# Sat_Cape_v7.net
KiCad netlist of a schematic drawn in EAGLE
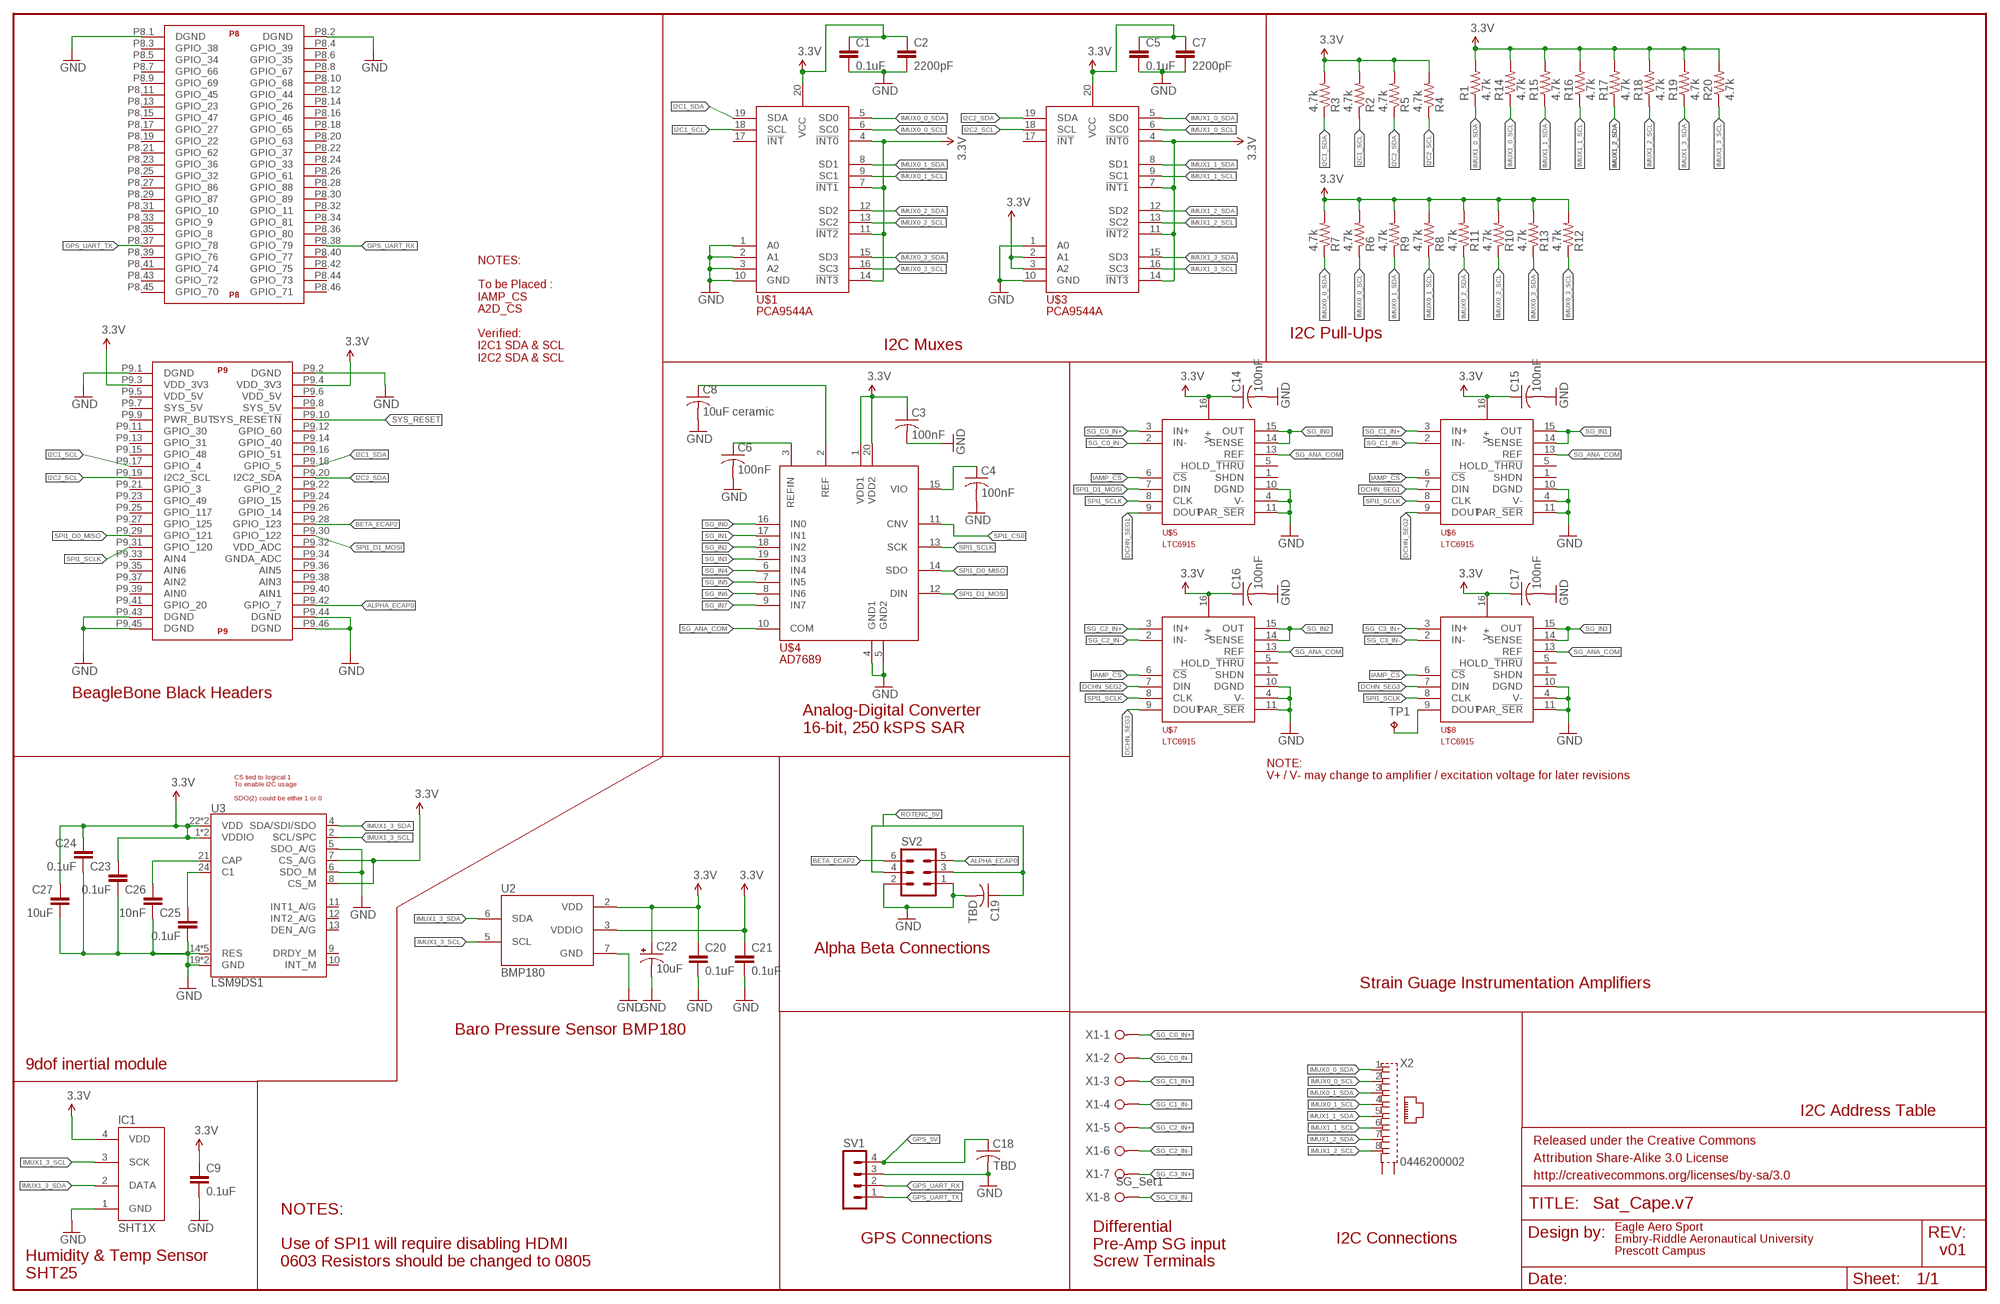
[diagram p0: schematic, sheet 1]

(export (version "E")
  (design (tool "Eeschema 10.0.6"))
  (components
    (comp (ref "C1")
      (value "0.1uF")
      (footprint "eagle-import:0603-CAP")
      (libsource (lib "eagle-import") (part "0.1UF-25V(+80/-20%)(0603)"))
    )
    (comp (ref "C2")
      (value "2200pF")
      (footprint "eagle-import:0603-CAP")
      (libsource (lib "eagle-import") (part "0.1UF-25V(+80/-20%)(0603)"))
    )
    (comp (ref "C3")
      (value "100nF")
      (footprint "eagle-import:C0805")
      (libsource (lib "eagle-import") (part "C-USC0805"))
    )
    (comp (ref "C4")
      (value "100nF")
      (footprint "eagle-import:C0805")
      (libsource (lib "eagle-import") (part "C-USC0805"))
    )
    (comp (ref "C5")
      (value "0.1uF")
      (footprint "eagle-import:0603-CAP")
      (libsource (lib "eagle-import") (part "0.1UF-25V(+80/-20%)(0603)"))
    )
    (comp (ref "C6")
      (value "100nF")
      (footprint "eagle-import:C0805")
      (libsource (lib "eagle-import") (part "C-USC0805"))
    )
    (comp (ref "C7")
      (value "2200pF")
      (footprint "eagle-import:0603-CAP")
      (libsource (lib "eagle-import") (part "0.1UF-25V(+80/-20%)(0603)"))
    )
    (comp (ref "C8")
      (value "10uF ceramic")
      (footprint "eagle-import:C0805")
      (libsource (lib "eagle-import") (part "C-USC0805"))
    )
    (comp (ref "C9")
      (value "0.1uF")
      (footprint "eagle-import:0603-CAP")
      (libsource (lib "eagle-import") (part "0.1UF-25V(+80/-20%)(0603)"))
    )
    (comp (ref "C14")
      (value "100nF")
      (footprint "eagle-import:C0805")
      (libsource (lib "eagle-import") (part "C-USC0805"))
    )
    (comp (ref "C15")
      (value "100nF")
      (footprint "eagle-import:C0805")
      (libsource (lib "eagle-import") (part "C-USC0805"))
    )
    (comp (ref "C16")
      (value "100nF")
      (footprint "eagle-import:C0805")
      (libsource (lib "eagle-import") (part "C-USC0805"))
    )
    (comp (ref "C17")
      (value "100nF")
      (footprint "eagle-import:C0805")
      (libsource (lib "eagle-import") (part "C-USC0805"))
    )
    (comp (ref "C18")
      (value "TBD")
      (footprint "eagle-import:C0805")
      (libsource (lib "eagle-import") (part "C-USC0805"))
    )
    (comp (ref "C19")
      (value "TBD")
      (footprint "eagle-import:C0805")
      (libsource (lib "eagle-import") (part "C-USC0805"))
    )
    (comp (ref "C20")
      (value "0.1uF")
      (footprint "eagle-import:0603-CAP")
      (libsource (lib "eagle-import") (part "CAP0603-CAP"))
    )
    (comp (ref "C21")
      (value "0.1uF")
      (footprint "eagle-import:0603-CAP")
      (libsource (lib "eagle-import") (part "CAP0603-CAP"))
    )
    (comp (ref "C22")
      (value "10uF")
      (footprint "eagle-import:EIA3216")
      (libsource (lib "eagle-import") (part "10UF-16V-10%(TANT)"))
    )
    (comp (ref "C23")
      (value "0.1uF")
      (footprint "eagle-import:0603-CAP")
      (libsource (lib "eagle-import") (part "0.1UF-25V(+80/-20%)(0603)"))
    )
    (comp (ref "C24")
      (value "0.1uF")
      (footprint "eagle-import:0603-CAP")
      (libsource (lib "eagle-import") (part "0.1UF-25V(+80/-20%)(0603)"))
    )
    (comp (ref "C25")
      (value "0.1uF")
      (footprint "eagle-import:0603-CAP")
      (libsource (lib "eagle-import") (part "0.1UF-25V(+80/-20%)(0603)"))
    )
    (comp (ref "C26")
      (value "10nF")
      (footprint "eagle-import:0603-CAP")
      (libsource (lib "eagle-import") (part "10NF/10000PF-50V-10%(0603)"))
    )
    (comp (ref "C27")
      (value "10uF")
      (footprint "eagle-import:0603-CAP")
      (libsource (lib "eagle-import") (part "10UF-6.3V-20%(0603)"))
    )
    (comp (ref "FRAME1")
      (value "FRAME-LEDGER")
      (footprint "eagle-import:CREATIVE_COMMONS")
      (libsource (lib "eagle-import") (part "FRAME-LEDGER"))
    )
    (comp (ref "IC1")
      (value "SHT1X")
      (footprint "eagle-import:SHT1X")
      (libsource (lib "eagle-import") (part "SHT1X"))
    )
    (comp (ref "R1")
      (value "4.7k")
      (footprint "eagle-import:R0805")
      (libsource (lib "eagle-import") (part "R-US_R0805"))
    )
    (comp (ref "R2")
      (value "4.7k")
      (footprint "eagle-import:0603-RES")
      (libsource (lib "eagle-import") (part "10KOHM1/10W1%(0603)0603"))
    )
    (comp (ref "R3")
      (value "4.7k")
      (footprint "eagle-import:0603-RES")
      (libsource (lib "eagle-import") (part "10KOHM1/10W1%(0603)0603"))
    )
    (comp (ref "R4")
      (value "4.7k")
      (footprint "eagle-import:0603-RES")
      (libsource (lib "eagle-import") (part "10KOHM1/10W1%(0603)0603"))
    )
    (comp (ref "R5")
      (value "4.7k")
      (footprint "eagle-import:0603-RES")
      (libsource (lib "eagle-import") (part "10KOHM1/10W1%(0603)0603"))
    )
    (comp (ref "R6")
      (value "4.7k")
      (footprint "eagle-import:0603-RES")
      (libsource (lib "eagle-import") (part "10KOHM1/10W1%(0603)0603"))
    )
    (comp (ref "R7")
      (value "4.7k")
      (footprint "eagle-import:0603-RES")
      (libsource (lib "eagle-import") (part "10KOHM1/10W1%(0603)0603"))
    )
    (comp (ref "R8")
      (value "4.7k")
      (footprint "eagle-import:0603-RES")
      (libsource (lib "eagle-import") (part "10KOHM1/10W1%(0603)0603"))
    )
    (comp (ref "R9")
      (value "4.7k")
      (footprint "eagle-import:0603-RES")
      (libsource (lib "eagle-import") (part "10KOHM1/10W1%(0603)0603"))
    )
    (comp (ref "R10")
      (value "4.7k")
      (footprint "eagle-import:0603-RES")
      (libsource (lib "eagle-import") (part "10KOHM1/10W1%(0603)0603"))
    )
    (comp (ref "R11")
      (value "4.7k")
      (footprint "eagle-import:0603-RES")
      (libsource (lib "eagle-import") (part "10KOHM1/10W1%(0603)0603"))
    )
    (comp (ref "R12")
      (value "4.7k")
      (footprint "eagle-import:0603-RES")
      (libsource (lib "eagle-import") (part "10KOHM1/10W1%(0603)0603"))
    )
    (comp (ref "R13")
      (value "4.7k")
      (footprint "eagle-import:0603-RES")
      (libsource (lib "eagle-import") (part "10KOHM1/10W1%(0603)0603"))
    )
    (comp (ref "R14")
      (value "4.7k")
      (footprint "eagle-import:R0805")
      (libsource (lib "eagle-import") (part "R-US_R0805"))
    )
    (comp (ref "R15")
      (value "4.7k")
      (footprint "eagle-import:R0805")
      (libsource (lib "eagle-import") (part "R-US_R0805"))
    )
    (comp (ref "R16")
      (value "4.7k")
      (footprint "eagle-import:R0805")
      (libsource (lib "eagle-import") (part "R-US_R0805"))
    )
    (comp (ref "R17")
      (value "4.7k")
      (footprint "eagle-import:R0805")
      (libsource (lib "eagle-import") (part "R-US_R0805"))
    )
    (comp (ref "R18")
      (value "4.7k")
      (footprint "eagle-import:R0805")
      (libsource (lib "eagle-import") (part "R-US_R0805"))
    )
    (comp (ref "R19")
      (value "4.7k")
      (footprint "eagle-import:R0805")
      (libsource (lib "eagle-import") (part "R-US_R0805"))
    )
    (comp (ref "R20")
      (value "4.7k")
      (footprint "eagle-import:R0805")
      (libsource (lib "eagle-import") (part "R-US_R0805"))
    )
    (comp (ref "SV1")
      (value "MA04-1")
      (footprint "eagle-import:MA04-1")
      (libsource (lib "eagle-import") (part "MA04-1"))
    )
    (comp (ref "SV2")
      (value "MA03-2")
      (footprint "eagle-import:MA03-2")
      (libsource (lib "eagle-import") (part "MA03-2"))
    )
    (comp (ref "TP1")
      (value "TPTP08R")
      (footprint "eagle-import:TP08R")
      (libsource (lib "eagle-import") (part "TPTP08R"))
    )
    (comp (ref "U$1")
      (value "PCA9544A")
      (footprint "eagle-import:TSSOP20")
      (libsource (lib "eagle-import") (part "PCA9544A"))
    )
    (comp (ref "U$2")
      (value "BEAGLE_BONE_BLACK_CAPE")
      (footprint "eagle-import:BEAGLE_BONE_BLACK_CAPE")
      (libsource (lib "eagle-import") (part "BEAGLE_BONE_BLACK_CAPE"))
    )
    (comp (ref "U$3")
      (value "PCA9544A")
      (footprint "eagle-import:TSSOP20")
      (libsource (lib "eagle-import") (part "PCA9544A"))
    )
    (comp (ref "U$4")
      (value "AD7689")
      (footprint "eagle-import:QFN20")
      (libsource (lib "eagle-import") (part "AD7689"))
    )
    (comp (ref "U$5")
      (value "LTC6915")
      (footprint "eagle-import:SSOP16")
      (libsource (lib "eagle-import") (part "LTC6915"))
    )
    (comp (ref "U$6")
      (value "LTC6915")
      (footprint "eagle-import:SSOP16")
      (libsource (lib "eagle-import") (part "LTC6915"))
    )
    (comp (ref "U$7")
      (value "LTC6915")
      (footprint "eagle-import:SSOP16")
      (libsource (lib "eagle-import") (part "LTC6915"))
    )
    (comp (ref "U$8")
      (value "LTC6915")
      (footprint "eagle-import:SSOP16")
      (libsource (lib "eagle-import") (part "LTC6915"))
    )
    (comp (ref "U2")
      (value "BMP180")
      (footprint "eagle-import:BMP180")
      (libsource (lib "eagle-import") (part "BMP180"))
    )
    (comp (ref "U3")
      (value "LSM9DS1")
      (footprint "eagle-import:LGA24-8X4")
      (libsource (lib "eagle-import") (part "LSM9DS1"))
    )
    (comp (ref "X1")
      (value "SG_Set1")
      (footprint "eagle-import:W237-8P")
      (libsource (lib "eagle-import") (part "W237-08P"))
    )
    (comp (ref "X2")
      (value "0446200002")
      (footprint "eagle-import:0446200002")
      (fields (field (name "MF") "MOLEX"))
      (libsource (lib "eagle-import") (part "0446200002"))
    )
  )
  (nets
    (net (code "1") (name "/IAMP_~{CS}") (class "Default")
      (node (ref "U$5") (pin "6") (pinfunction "~{CS}_6") (pintype "bidirectional"))
      (node (ref "U$6") (pin "6") (pinfunction "~{CS}_6") (pintype "bidirectional"))
      (node (ref "U$7") (pin "6") (pinfunction "~{CS}_6") (pintype "bidirectional"))
      (node (ref "U$8") (pin "6") (pinfunction "~{CS}_6") (pintype "bidirectional"))
    )
    (net (code "2") (name "3.3V") (class "Default")
      (node (ref "C1") (pin "1") (pinfunction "1_1") (pintype "passive"))
      (node (ref "C14") (pin "1") (pinfunction "1_1") (pintype "passive"))
      (node (ref "C15") (pin "1") (pinfunction "1_1") (pintype "passive"))
      (node (ref "C16") (pin "1") (pinfunction "1_1") (pintype "passive"))
      (node (ref "C17") (pin "1") (pinfunction "1_1") (pintype "passive"))
      (node (ref "C2") (pin "1") (pinfunction "1_1") (pintype "passive"))
      (node (ref "C20") (pin "1") (pinfunction "1_1") (pintype "passive"))
      (node (ref "C21") (pin "1") (pinfunction "1_1") (pintype "passive"))
      (node (ref "C22") (pin "A") (pinfunction "+_A") (pintype "passive"))
      (node (ref "C23") (pin "1") (pinfunction "1_1") (pintype "passive"))
      (node (ref "C24") (pin "1") (pinfunction "1_1") (pintype "passive"))
      (node (ref "C27") (pin "1") (pinfunction "1_1") (pintype "passive"))
      (node (ref "C3") (pin "1") (pinfunction "1_1") (pintype "passive"))
      (node (ref "C5") (pin "1") (pinfunction "1_1") (pintype "passive"))
      (node (ref "C7") (pin "1") (pinfunction "1_1") (pintype "passive"))
      (node (ref "C9") (pin "1") (pinfunction "1_1") (pintype "passive"))
      (node (ref "IC1") (pin "4") (pinfunction "VDD_4") (pintype "power_in"))
      (node (ref "R1") (pin "2") (pinfunction "2_2") (pintype "passive"))
      (node (ref "R10") (pin "2") (pinfunction "2_2") (pintype "passive"))
      (node (ref "R11") (pin "2") (pinfunction "2_2") (pintype "passive"))
      (node (ref "R12") (pin "2") (pinfunction "2_2") (pintype "passive"))
      (node (ref "R13") (pin "2") (pinfunction "2_2") (pintype "passive"))
      (node (ref "R14") (pin "2") (pinfunction "2_2") (pintype "passive"))
      (node (ref "R15") (pin "2") (pinfunction "2_2") (pintype "passive"))
      (node (ref "R16") (pin "2") (pinfunction "2_2") (pintype "passive"))
      (node (ref "R17") (pin "2") (pinfunction "2_2") (pintype "passive"))
      (node (ref "R18") (pin "2") (pinfunction "2_2") (pintype "passive"))
      (node (ref "R19") (pin "2") (pinfunction "2_2") (pintype "passive"))
      (node (ref "R2") (pin "2") (pinfunction "2_2") (pintype "passive"))
      (node (ref "R20") (pin "2") (pinfunction "2_2") (pintype "passive"))
      (node (ref "R3") (pin "2") (pinfunction "2_2") (pintype "passive"))
      (node (ref "R4") (pin "2") (pinfunction "2_2") (pintype "passive"))
      (node (ref "R5") (pin "2") (pinfunction "2_2") (pintype "passive"))
      (node (ref "R6") (pin "2") (pinfunction "2_2") (pintype "passive"))
      (node (ref "R7") (pin "2") (pinfunction "2_2") (pintype "passive"))
      (node (ref "R8") (pin "2") (pinfunction "2_2") (pintype "passive"))
      (node (ref "R9") (pin "2") (pinfunction "2_2") (pintype "passive"))
      (node (ref "U$1") (pin "11") (pinfunction "~{INT2}_11") (pintype "input"))
      (node (ref "U$1") (pin "14") (pinfunction "~{INT3}_14") (pintype "input"))
      (node (ref "U$1") (pin "20") (pinfunction "VCC_20") (pintype "power_in"))
      (node (ref "U$1") (pin "4") (pinfunction "~{INT0}_4") (pintype "input"))
      (node (ref "U$1") (pin "7") (pinfunction "~{INT1}_7") (pintype "input"))
      (node (ref "U$2") (pin "P9.3") (pinfunction "VDD_3V3_P9.3") (pintype "bidirectional"))
      (node (ref "U$2") (pin "P9.4") (pinfunction "VDD_3V3_P9.4") (pintype "bidirectional"))
      (node (ref "U$3") (pin "11") (pinfunction "~{INT2}_11") (pintype "input"))
      (node (ref "U$3") (pin "14") (pinfunction "~{INT3}_14") (pintype "input"))
      (node (ref "U$3") (pin "2") (pinfunction "A1_2") (pintype "input"))
      (node (ref "U$3") (pin "20") (pinfunction "VCC_20") (pintype "power_in"))
      (node (ref "U$3") (pin "3") (pinfunction "A2_3") (pintype "input"))
      (node (ref "U$3") (pin "4") (pinfunction "~{INT0}_4") (pintype "input"))
      (node (ref "U$3") (pin "7") (pinfunction "~{INT1}_7") (pintype "input"))
      (node (ref "U$4") (pin "1") (pinfunction "VDD1_1") (pintype "bidirectional"))
      (node (ref "U$4") (pin "20") (pinfunction "VDD2_20") (pintype "bidirectional"))
      (node (ref "U$5") (pin "16") (pinfunction "V+_16") (pintype "bidirectional"))
      (node (ref "U$6") (pin "16") (pinfunction "V+_16") (pintype "bidirectional"))
      (node (ref "U$7") (pin "16") (pinfunction "V+_16") (pintype "bidirectional"))
      (node (ref "U$8") (pin "16") (pinfunction "V+_16") (pintype "bidirectional"))
      (node (ref "U2") (pin "2") (pinfunction "VDD_2") (pintype "power_in"))
      (node (ref "U2") (pin "3") (pinfunction "VDDIO_3") (pintype "power_in"))
      (node (ref "U3") (pin "1") (pinfunction "VDDIO_1") (pintype "bidirectional"))
      (node (ref "U3") (pin "22") (pinfunction "VDD_22") (pintype "bidirectional"))
      (node (ref "U3") (pin "23") (pinfunction "VDD_23") (pintype "bidirectional"))
      (node (ref "U3") (pin "3") (pinfunction "VDDIO_3") (pintype "bidirectional"))
      (node (ref "U3") (pin "7") (pinfunction "CS_A/G_7") (pintype "bidirectional"))
      (node (ref "U3") (pin "8") (pinfunction "CS_M_8") (pintype "bidirectional"))
    )
    (net (code "3") (name "ALPHA_ECAP0") (class "Default")
      (node (ref "SV2") (pin "5") (pinfunction "5_5") (pintype "passive"))
      (node (ref "U$2") (pin "P9.42") (pinfunction "GPIO_7_P9.42") (pintype "bidirectional"))
    )
    (net (code "4") (name "BETA_ECAP2") (class "Default")
      (node (ref "SV2") (pin "6") (pinfunction "6_6") (pintype "passive"))
      (node (ref "U$2") (pin "P9.28") (pinfunction "GPIO_123_P9.28") (pintype "bidirectional"))
    )
    (net (code "5") (name "DCHN_SEG1") (class "Default")
      (node (ref "U$5") (pin "9") (pinfunction "DOUT_9") (pintype "bidirectional"))
      (node (ref "U$6") (pin "7") (pinfunction "DIN_7") (pintype "bidirectional"))
    )
    (net (code "6") (name "DCHN_SEG2") (class "Default")
      (node (ref "U$6") (pin "9") (pinfunction "DOUT_9") (pintype "bidirectional"))
      (node (ref "U$7") (pin "7") (pinfunction "DIN_7") (pintype "bidirectional"))
    )
    (net (code "7") (name "DCHN_SEG3") (class "Default")
      (node (ref "U$7") (pin "9") (pinfunction "DOUT_9") (pintype "bidirectional"))
      (node (ref "U$8") (pin "7") (pinfunction "DIN_7") (pintype "bidirectional"))
    )
    (net (code "8") (name "GND") (class "Default")
      (node (ref "C1") (pin "2") (pinfunction "2_2") (pintype "passive"))
      (node (ref "C14") (pin "2") (pinfunction "2_2") (pintype "passive"))
      (node (ref "C15") (pin "2") (pinfunction "2_2") (pintype "passive"))
      (node (ref "C16") (pin "2") (pinfunction "2_2") (pintype "passive"))
      (node (ref "C17") (pin "2") (pinfunction "2_2") (pintype "passive"))
      (node (ref "C18") (pin "2") (pinfunction "2_2") (pintype "passive"))
      (node (ref "C19") (pin "2") (pinfunction "2_2") (pintype "passive"))
      (node (ref "C2") (pin "2") (pinfunction "2_2") (pintype "passive"))
      (node (ref "C20") (pin "2") (pinfunction "2_2") (pintype "passive"))
      (node (ref "C21") (pin "2") (pinfunction "2_2") (pintype "passive"))
      (node (ref "C22") (pin "C") (pinfunction "-_C") (pintype "passive"))
      (node (ref "C23") (pin "2") (pinfunction "2_2") (pintype "passive"))
      (node (ref "C24") (pin "2") (pinfunction "2_2") (pintype "passive"))
      (node (ref "C25") (pin "2") (pinfunction "2_2") (pintype "passive"))
      (node (ref "C26") (pin "2") (pinfunction "2_2") (pintype "passive"))
      (node (ref "C27") (pin "2") (pinfunction "2_2") (pintype "passive"))
      (node (ref "C3") (pin "2") (pinfunction "2_2") (pintype "passive"))
      (node (ref "C4") (pin "2") (pinfunction "2_2") (pintype "passive"))
      (node (ref "C5") (pin "2") (pinfunction "2_2") (pintype "passive"))
      (node (ref "C6") (pin "2") (pinfunction "2_2") (pintype "passive"))
      (node (ref "C7") (pin "2") (pinfunction "2_2") (pintype "passive"))
      (node (ref "C8") (pin "2") (pinfunction "2_2") (pintype "passive"))
      (node (ref "C9") (pin "2") (pinfunction "2_2") (pintype "passive"))
      (node (ref "IC1") (pin "1") (pinfunction "GND_1") (pintype "power_in"))
      (node (ref "SV1") (pin "3") (pinfunction "3_3") (pintype "passive"))
      (node (ref "SV2") (pin "1") (pinfunction "1_1") (pintype "passive"))
      (node (ref "SV2") (pin "2") (pinfunction "2_2") (pintype "passive"))
      (node (ref "U$1") (pin "1") (pinfunction "A0_1") (pintype "input"))
      (node (ref "U$1") (pin "10") (pinfunction "GND_10") (pintype "power_in"))
      (node (ref "U$1") (pin "2") (pinfunction "A1_2") (pintype "input"))
      (node (ref "U$1") (pin "3") (pinfunction "A2_3") (pintype "input"))
      (node (ref "U$2") (pin "P8.1") (pinfunction "DGND_P8.1") (pintype "bidirectional"))
      (node (ref "U$2") (pin "P8.2") (pinfunction "DGND_P8.2") (pintype "bidirectional"))
      (node (ref "U$2") (pin "P9.1") (pinfunction "DGND_P9.1") (pintype "bidirectional"))
      (node (ref "U$2") (pin "P9.2") (pinfunction "DGND_P9.2") (pintype "bidirectional"))
      (node (ref "U$2") (pin "P9.43") (pinfunction "DGND_P9.43") (pintype "bidirectional"))
      (node (ref "U$2") (pin "P9.44") (pinfunction "DGND_P9.44") (pintype "bidirectional"))
      (node (ref "U$2") (pin "P9.45") (pinfunction "DGND_P9.45") (pintype "bidirectional"))
      (node (ref "U$2") (pin "P9.46") (pinfunction "DGND_P9.46") (pintype "bidirectional"))
      (node (ref "U$3") (pin "1") (pinfunction "A0_1") (pintype "input"))
      (node (ref "U$3") (pin "10") (pinfunction "GND_10") (pintype "power_in"))
      (node (ref "U$4") (pin "4") (pinfunction "GND1_4") (pintype "bidirectional"))
      (node (ref "U$4") (pin "5") (pinfunction "GND2_5") (pintype "bidirectional"))
      (node (ref "U$5") (pin "10") (pinfunction "DGND_10") (pintype "bidirectional"))
      (node (ref "U$5") (pin "11") (pinfunction "PAR_~{SER}_11") (pintype "bidirectional"))
      (node (ref "U$5") (pin "4") (pinfunction "V-_4") (pintype "bidirectional"))
      (node (ref "U$6") (pin "10") (pinfunction "DGND_10") (pintype "bidirectional"))
      (node (ref "U$6") (pin "11") (pinfunction "PAR_~{SER}_11") (pintype "bidirectional"))
      (node (ref "U$6") (pin "4") (pinfunction "V-_4") (pintype "bidirectional"))
      (node (ref "U$7") (pin "10") (pinfunction "DGND_10") (pintype "bidirectional"))
      (node (ref "U$7") (pin "11") (pinfunction "PAR_~{SER}_11") (pintype "bidirectional"))
      (node (ref "U$7") (pin "4") (pinfunction "V-_4") (pintype "bidirectional"))
      (node (ref "U$8") (pin "10") (pinfunction "DGND_10") (pintype "bidirectional"))
      (node (ref "U$8") (pin "11") (pinfunction "PAR_~{SER}_11") (pintype "bidirectional"))
      (node (ref "U$8") (pin "4") (pinfunction "V-_4") (pintype "bidirectional"))
      (node (ref "U2") (pin "7") (pinfunction "GND_7") (pintype "power_in"))
      (node (ref "U3") (pin "14") (pinfunction "RES_14") (pintype "bidirectional"))
      (node (ref "U3") (pin "15") (pinfunction "RES_15") (pintype "bidirectional"))
      (node (ref "U3") (pin "16") (pinfunction "RES_16") (pintype "bidirectional"))
      (node (ref "U3") (pin "17") (pinfunction "RES_17") (pintype "bidirectional"))
      (node (ref "U3") (pin "18") (pinfunction "RES_18") (pintype "bidirectional"))
      (node (ref "U3") (pin "19") (pinfunction "GND_19") (pintype "bidirectional"))
      (node (ref "U3") (pin "20") (pinfunction "GND_20") (pintype "bidirectional"))
      (node (ref "U3") (pin "5") (pinfunction "SDO_A/G_5") (pintype "bidirectional"))
      (node (ref "U3") (pin "6") (pinfunction "SDO_M_6") (pintype "bidirectional"))
    )
    (net (code "9") (name "GPS_5V") (class "Default")
      (node (ref "C18") (pin "1") (pinfunction "1_1") (pintype "passive"))
      (node (ref "SV1") (pin "4") (pinfunction "4_4") (pintype "passive"))
    )
    (net (code "10") (name "GPS_UART_RX") (class "Default")
      (node (ref "SV1") (pin "2") (pinfunction "2_2") (pintype "passive"))
      (node (ref "U$2") (pin "P8.38") (pinfunction "GPIO_79_P8.38") (pintype "bidirectional"))
    )
    (net (code "11") (name "GPS_UART_TX") (class "Default")
      (node (ref "SV1") (pin "1") (pinfunction "1_1") (pintype "passive"))
      (node (ref "U$2") (pin "P8.37") (pinfunction "GPIO_78_P8.37") (pintype "bidirectional"))
    )
    (net (code "12") (name "I2C1_SCL") (class "Default")
      (node (ref "R2") (pin "1") (pinfunction "1_1") (pintype "passive"))
      (node (ref "U$1") (pin "18") (pinfunction "SCL_18") (pintype "input"))
      (node (ref "U$2") (pin "P9.17") (pinfunction "GPIO_4_P9.17") (pintype "bidirectional"))
    )
    (net (code "13") (name "I2C1_SDA") (class "Default")
      (node (ref "R3") (pin "1") (pinfunction "1_1") (pintype "passive"))
      (node (ref "U$1") (pin "19") (pinfunction "SDA_19") (pintype "bidirectional"))
      (node (ref "U$2") (pin "P9.18") (pinfunction "GPIO_5_P9.18") (pintype "bidirectional"))
    )
    (net (code "14") (name "I2C2_SCL") (class "Default")
      (node (ref "R4") (pin "1") (pinfunction "1_1") (pintype "passive"))
      (node (ref "U$2") (pin "P9.19") (pinfunction "I2C2_SCL_P9.19") (pintype "bidirectional"))
      (node (ref "U$3") (pin "18") (pinfunction "SCL_18") (pintype "input"))
    )
    (net (code "15") (name "I2C2_SDA") (class "Default")
      (node (ref "R5") (pin "1") (pinfunction "1_1") (pintype "passive"))
      (node (ref "U$2") (pin "P9.20") (pinfunction "I2C2_SDA_P9.20") (pintype "bidirectional"))
      (node (ref "U$3") (pin "19") (pinfunction "SDA_19") (pintype "bidirectional"))
    )
    (net (code "16") (name "IMUX0_0_SCL") (class "Default")
      (node (ref "R6") (pin "1") (pinfunction "1_1") (pintype "passive"))
      (node (ref "U$1") (pin "6") (pinfunction "SC0_6") (pintype "output"))
      (node (ref "X2") (pin "2") (pinfunction "2_2") (pintype "passive"))
    )
    (net (code "17") (name "IMUX0_0_SDA") (class "Default")
      (node (ref "R7") (pin "1") (pinfunction "1_1") (pintype "passive"))
      (node (ref "U$1") (pin "5") (pinfunction "SD0_5") (pintype "bidirectional"))
      (node (ref "X2") (pin "1") (pinfunction "1_1") (pintype "passive"))
    )
    (net (code "18") (name "IMUX0_1_SCL") (class "Default")
      (node (ref "R8") (pin "1") (pinfunction "1_1") (pintype "passive"))
      (node (ref "U$1") (pin "9") (pinfunction "SC1_9") (pintype "output"))
      (node (ref "X2") (pin "4") (pinfunction "4_4") (pintype "passive"))
    )
    (net (code "19") (name "IMUX0_1_SDA") (class "Default")
      (node (ref "R9") (pin "1") (pinfunction "1_1") (pintype "passive"))
      (node (ref "U$1") (pin "8") (pinfunction "SD1_8") (pintype "bidirectional"))
      (node (ref "X2") (pin "3") (pinfunction "3_3") (pintype "passive"))
    )
    (net (code "20") (name "IMUX0_2_SCL") (class "Default")
      (node (ref "R10") (pin "1") (pinfunction "1_1") (pintype "passive"))
      (node (ref "U$1") (pin "13") (pinfunction "SC2_13") (pintype "output"))
    )
    (net (code "21") (name "IMUX0_2_SDA") (class "Default")
      (node (ref "R11") (pin "1") (pinfunction "1_1") (pintype "passive"))
      (node (ref "U$1") (pin "12") (pinfunction "SD2_12") (pintype "bidirectional"))
    )
    (net (code "22") (name "IMUX0_3_SCL") (class "Default")
      (node (ref "R12") (pin "1") (pinfunction "1_1") (pintype "passive"))
      (node (ref "U$1") (pin "16") (pinfunction "SC3_16") (pintype "output"))
    )
    (net (code "23") (name "IMUX0_3_SDA") (class "Default")
      (node (ref "R13") (pin "1") (pinfunction "1_1") (pintype "passive"))
      (node (ref "U$1") (pin "15") (pinfunction "SD3_15") (pintype "bidirectional"))
    )
    (net (code "24") (name "IMUX1_0_SCL") (class "Default")
      (node (ref "R14") (pin "1") (pinfunction "1_1") (pintype "passive"))
      (node (ref "U$3") (pin "6") (pinfunction "SC0_6") (pintype "output"))
    )
    (net (code "25") (name "IMUX1_0_SDA") (class "Default")
      (node (ref "R1") (pin "1") (pinfunction "1_1") (pintype "passive"))
      (node (ref "U$3") (pin "5") (pinfunction "SD0_5") (pintype "bidirectional"))
    )
    (net (code "26") (name "IMUX1_1_SCL") (class "Default")
      (node (ref "R16") (pin "1") (pinfunction "1_1") (pintype "passive"))
      (node (ref "U$3") (pin "9") (pinfunction "SC1_9") (pintype "output"))
      (node (ref "X2") (pin "6") (pinfunction "6_6") (pintype "passive"))
    )
    (net (code "27") (name "IMUX1_1_SDA") (class "Default")
      (node (ref "R15") (pin "1") (pinfunction "1_1") (pintype "passive"))
      (node (ref "U$3") (pin "8") (pinfunction "SD1_8") (pintype "bidirectional"))
      (node (ref "X2") (pin "5") (pinfunction "5_5") (pintype "passive"))
    )
    (net (code "28") (name "IMUX1_2_SCL") (class "Default")
      (node (ref "R18") (pin "1") (pinfunction "1_1") (pintype "passive"))
      (node (ref "U$3") (pin "13") (pinfunction "SC2_13") (pintype "output"))
      (node (ref "X2") (pin "8") (pinfunction "8_8") (pintype "passive"))
    )
    (net (code "29") (name "IMUX1_2_SDA") (class "Default")
      (node (ref "R17") (pin "1") (pinfunction "1_1") (pintype "passive"))
      (node (ref "U$3") (pin "12") (pinfunction "SD2_12") (pintype "bidirectional"))
      (node (ref "X2") (pin "7") (pinfunction "7_7") (pintype "passive"))
    )
    (net (code "30") (name "IMUX1_3_SCL") (class "Default")
      (node (ref "IC1") (pin "3") (pinfunction "SCK_3") (pintype "input"))
      (node (ref "R20") (pin "1") (pinfunction "1_1") (pintype "passive"))
      (node (ref "U$3") (pin "16") (pinfunction "SC3_16") (pintype "output"))
      (node (ref "U2") (pin "5") (pinfunction "SCL_5") (pintype "input"))
      (node (ref "U3") (pin "2") (pinfunction "SCL/SPC_2") (pintype "bidirectional"))
    )
    (net (code "31") (name "IMUX1_3_SDA") (class "Default")
      (node (ref "IC1") (pin "2") (pinfunction "DATA_2") (pintype "open_collector"))
      (node (ref "R19") (pin "1") (pinfunction "1_1") (pintype "passive"))
      (node (ref "U$3") (pin "15") (pinfunction "SD3_15") (pintype "bidirectional"))
      (node (ref "U2") (pin "6") (pinfunction "SDA_6") (pintype "bidirectional"))
      (node (ref "U3") (pin "4") (pinfunction "SDA/SDI/SDO_4") (pintype "bidirectional"))
    )
    (net (code "32") (name "Net-(U$4-REF)") (class "Default")
      (node (ref "C8") (pin "1") (pinfunction "1_1") (pintype "passive"))
      (node (ref "U$4") (pin "2") (pinfunction "REF_2") (pintype "bidirectional"))
    )
    (net (code "33") (name "Net-(U$4-REFIN)") (class "Default")
      (node (ref "C6") (pin "1") (pinfunction "1_1") (pintype "passive"))
      (node (ref "U$4") (pin "3") (pinfunction "REFIN_3") (pintype "bidirectional"))
    )
    (net (code "34") (name "Net-(U$4-VIO)") (class "Default")
      (node (ref "C4") (pin "1") (pinfunction "1_1") (pintype "passive"))
      (node (ref "U$4") (pin "15") (pinfunction "VIO_15") (pintype "bidirectional"))
    )
    (net (code "35") (name "Net-(U$8-DOUT)") (class "Default")
      (node (ref "TP1") (pin "TP") (pinfunction "TP_TP") (pintype "input"))
      (node (ref "U$8") (pin "9") (pinfunction "DOUT_9") (pintype "bidirectional"))
    )
    (net (code "36") (name "Net-(U3-C1)") (class "Default")
      (node (ref "C25") (pin "1") (pinfunction "1_1") (pintype "passive"))
      (node (ref "U3") (pin "24") (pinfunction "C1_24") (pintype "bidirectional"))
    )
    (net (code "37") (name "Net-(U3-CAP)") (class "Default")
      (node (ref "C26") (pin "1") (pinfunction "1_1") (pintype "passive"))
      (node (ref "U3") (pin "21") (pinfunction "CAP_21") (pintype "bidirectional"))
    )
    (net (code "38") (name "ROTENC_5V") (class "Default")
      (node (ref "C19") (pin "1") (pinfunction "1_1") (pintype "passive"))
      (node (ref "SV2") (pin "3") (pinfunction "3_3") (pintype "passive"))
      (node (ref "SV2") (pin "4") (pinfunction "4_4") (pintype "passive"))
    )
    (net (code "39") (name "SG_ANA_COM") (class "Default")
      (node (ref "U$4") (pin "10") (pinfunction "COM_10") (pintype "bidirectional"))
      (node (ref "U$5") (pin "13") (pinfunction "REF_13") (pintype "bidirectional"))
      (node (ref "U$6") (pin "13") (pinfunction "REF_13") (pintype "bidirectional"))
      (node (ref "U$7") (pin "13") (pinfunction "REF_13") (pintype "bidirectional"))
      (node (ref "U$8") (pin "13") (pinfunction "REF_13") (pintype "bidirectional"))
    )
    (net (code "40") (name "SG_C0_IN+") (class "Default")
      (node (ref "U$5") (pin "3") (pinfunction "IN+_3") (pintype "bidirectional"))
      (node (ref "X1") (pin "1") (pinfunction "KL_1") (pintype "passive"))
    )
    (net (code "41") (name "SG_C0_IN-") (class "Default")
      (node (ref "U$5") (pin "2") (pinfunction "IN-_2") (pintype "bidirectional"))
      (node (ref "X1") (pin "2") (pinfunction "KL_2") (pintype "passive"))
    )
    (net (code "42") (name "SG_C1_IN+") (class "Default")
      (node (ref "U$6") (pin "3") (pinfunction "IN+_3") (pintype "bidirectional"))
      (node (ref "X1") (pin "3") (pinfunction "KL_3") (pintype "passive"))
    )
    (net (code "43") (name "SG_C1_IN-") (class "Default")
      (node (ref "U$6") (pin "2") (pinfunction "IN-_2") (pintype "bidirectional"))
      (node (ref "X1") (pin "4") (pinfunction "KL_4") (pintype "passive"))
    )
    (net (code "44") (name "SG_C2_IN+") (class "Default")
      (node (ref "U$7") (pin "3") (pinfunction "IN+_3") (pintype "bidirectional"))
      (node (ref "X1") (pin "5") (pinfunction "KL_5") (pintype "passive"))
    )
    (net (code "45") (name "SG_C2_IN-") (class "Default")
      (node (ref "U$7") (pin "2") (pinfunction "IN-_2") (pintype "bidirectional"))
      (node (ref "X1") (pin "6") (pinfunction "KL_6") (pintype "passive"))
    )
    (net (code "46") (name "SG_C3_IN+") (class "Default")
      (node (ref "U$8") (pin "3") (pinfunction "IN+_3") (pintype "bidirectional"))
      (node (ref "X1") (pin "7") (pinfunction "KL_7") (pintype "passive"))
    )
    (net (code "47") (name "SG_C3_IN-") (class "Default")
      (node (ref "U$8") (pin "2") (pinfunction "IN-_2") (pintype "bidirectional"))
      (node (ref "X1") (pin "8") (pinfunction "KL_8") (pintype "passive"))
    )
    (net (code "48") (name "SG_IN0") (class "Default")
      (node (ref "U$4") (pin "16") (pinfunction "IN0_16") (pintype "bidirectional"))
      (node (ref "U$5") (pin "14") (pinfunction "SENSE_14") (pintype "bidirectional"))
      (node (ref "U$5") (pin "15") (pinfunction "OUT_15") (pintype "bidirectional"))
    )
    (net (code "49") (name "SG_IN1") (class "Default")
      (node (ref "U$4") (pin "17") (pinfunction "IN1_17") (pintype "bidirectional"))
      (node (ref "U$6") (pin "14") (pinfunction "SENSE_14") (pintype "bidirectional"))
      (node (ref "U$6") (pin "15") (pinfunction "OUT_15") (pintype "bidirectional"))
    )
    (net (code "50") (name "SG_IN2") (class "Default")
      (node (ref "U$4") (pin "18") (pinfunction "IN2_18") (pintype "bidirectional"))
      (node (ref "U$7") (pin "14") (pinfunction "SENSE_14") (pintype "bidirectional"))
      (node (ref "U$7") (pin "15") (pinfunction "OUT_15") (pintype "bidirectional"))
    )
    (net (code "51") (name "SG_IN3") (class "Default")
      (node (ref "U$4") (pin "19") (pinfunction "IN3_19") (pintype "bidirectional"))
      (node (ref "U$8") (pin "14") (pinfunction "SENSE_14") (pintype "bidirectional"))
      (node (ref "U$8") (pin "15") (pinfunction "OUT_15") (pintype "bidirectional"))
    )
    (net (code "52") (name "SG_IN4") (class "Default")
      (node (ref "U$4") (pin "6") (pinfunction "IN4_6") (pintype "bidirectional"))
    )
    (net (code "53") (name "SG_IN5") (class "Default")
      (node (ref "U$4") (pin "7") (pinfunction "IN5_7") (pintype "bidirectional"))
    )
    (net (code "54") (name "SG_IN6") (class "Default")
      (node (ref "U$4") (pin "8") (pinfunction "IN6_8") (pintype "bidirectional"))
    )
    (net (code "55") (name "SG_IN7") (class "Default")
      (node (ref "U$4") (pin "9") (pinfunction "IN7_9") (pintype "bidirectional"))
    )
    (net (code "56") (name "SPI1_CS0") (class "Default")
      (node (ref "U$4") (pin "11") (pinfunction "CNV_11") (pintype "bidirectional"))
    )
    (net (code "57") (name "SPI1_D0_MISO") (class "Default")
      (node (ref "U$2") (pin "P9.29") (pinfunction "GPIO_121_P9.29") (pintype "bidirectional"))
      (node (ref "U$4") (pin "14") (pinfunction "SDO_14") (pintype "bidirectional"))
    )
    (net (code "58") (name "SPI1_D1_MOSI") (class "Default")
      (node (ref "U$2") (pin "P9.30") (pinfunction "GPIO_122_P9.30") (pintype "bidirectional"))
      (node (ref "U$4") (pin "12") (pinfunction "DIN_12") (pintype "bidirectional"))
      (node (ref "U$5") (pin "7") (pinfunction "DIN_7") (pintype "bidirectional"))
    )
    (net (code "59") (name "SPI1_SCLK") (class "Default")
      (node (ref "U$2") (pin "P9.31") (pinfunction "GPIO_120_P9.31") (pintype "bidirectional"))
      (node (ref "U$4") (pin "13") (pinfunction "SCK_13") (pintype "bidirectional"))
      (node (ref "U$5") (pin "8") (pinfunction "CLK_8") (pintype "bidirectional"))
      (node (ref "U$6") (pin "8") (pinfunction "CLK_8") (pintype "bidirectional"))
      (node (ref "U$7") (pin "8") (pinfunction "CLK_8") (pintype "bidirectional"))
      (node (ref "U$8") (pin "8") (pinfunction "CLK_8") (pintype "bidirectional"))
    )
    (net (code "60") (name "SYS_RESET") (class "Default")
      (node (ref "U$2") (pin "P9.10") (pinfunction "SYS_RESET~{N}_P9.10") (pintype "bidirectional"))
    )
    (net (code "61") (name "unconnected-(U$1-~{INT}-Pad17)") (class "Default")
      (node (ref "U$1") (pin "17") (pinfunction "~{INT}_17") (pintype "output"))
    )
    (net (code "62") (name "unconnected-(U$2A-GPIO_8-PadP8.35)") (class "Default")
      (node (ref "U$2") (pin "P8.35") (pinfunction "GPIO_8_P8.35") (pintype "bidirectional"))
    )
    (net (code "63") (name "unconnected-(U$2A-GPIO_9-PadP8.33)") (class "Default")
      (node (ref "U$2") (pin "P8.33") (pinfunction "GPIO_9_P8.33") (pintype "bidirectional"))
    )
    (net (code "64") (name "unconnected-(U$2A-GPIO_10-PadP8.31)") (class "Default")
      (node (ref "U$2") (pin "P8.31") (pinfunction "GPIO_10_P8.31") (pintype "bidirectional"))
    )
    (net (code "65") (name "unconnected-(U$2A-GPIO_11-PadP8.32)") (class "Default")
      (node (ref "U$2") (pin "P8.32") (pinfunction "GPIO_11_P8.32") (pintype "bidirectional"))
    )
    (net (code "66") (name "unconnected-(U$2A-GPIO_22-PadP8.19)") (class "Default")
      (node (ref "U$2") (pin "P8.19") (pinfunction "GPIO_22_P8.19") (pintype "bidirectional"))
    )
    (net (code "67") (name "unconnected-(U$2A-GPIO_23-PadP8.13)") (class "Default")
      (node (ref "U$2") (pin "P8.13") (pinfunction "GPIO_23_P8.13") (pintype "bidirectional"))
    )
    (net (code "68") (name "unconnected-(U$2A-GPIO_26-PadP8.14)") (class "Default")
      (node (ref "U$2") (pin "P8.14") (pinfunction "GPIO_26_P8.14") (pintype "bidirectional"))
    )
    (net (code "69") (name "unconnected-(U$2A-GPIO_27-PadP8.17)") (class "Default")
      (node (ref "U$2") (pin "P8.17") (pinfunction "GPIO_27_P8.17") (pintype "bidirectional"))
    )
    (net (code "70") (name "unconnected-(U$2A-GPIO_32-PadP8.25)") (class "Default")
      (node (ref "U$2") (pin "P8.25") (pinfunction "GPIO_32_P8.25") (pintype "bidirectional"))
    )
    (net (code "71") (name "unconnected-(U$2A-GPIO_33-PadP8.24)") (class "Default")
      (node (ref "U$2") (pin "P8.24") (pinfunction "GPIO_33_P8.24") (pintype "bidirectional"))
    )
    (net (code "72") (name "unconnected-(U$2A-GPIO_34-PadP8.5)") (class "Default")
      (node (ref "U$2") (pin "P8.5") (pinfunction "GPIO_34_P8.5") (pintype "bidirectional"))
    )
    (net (code "73") (name "unconnected-(U$2A-GPIO_35-PadP8.6)") (class "Default")
      (node (ref "U$2") (pin "P8.6") (pinfunction "GPIO_35_P8.6") (pintype "bidirectional"))
    )
    (net (code "74") (name "unconnected-(U$2A-GPIO_36-PadP8.23)") (class "Default")
      (node (ref "U$2") (pin "P8.23") (pinfunction "GPIO_36_P8.23") (pintype "bidirectional"))
    )
    (net (code "75") (name "unconnected-(U$2A-GPIO_37-PadP8.22)") (class "Default")
      (node (ref "U$2") (pin "P8.22") (pinfunction "GPIO_37_P8.22") (pintype "bidirectional"))
    )
    (net (code "76") (name "unconnected-(U$2A-GPIO_38-PadP8.3)") (class "Default")
      (node (ref "U$2") (pin "P8.3") (pinfunction "GPIO_38_P8.3") (pintype "bidirectional"))
    )
    (net (code "77") (name "unconnected-(U$2A-GPIO_39-PadP8.4)") (class "Default")
      (node (ref "U$2") (pin "P8.4") (pinfunction "GPIO_39_P8.4") (pintype "bidirectional"))
    )
    (net (code "78") (name "unconnected-(U$2A-GPIO_44-PadP8.12)") (class "Default")
      (node (ref "U$2") (pin "P8.12") (pinfunction "GPIO_44_P8.12") (pintype "bidirectional"))
    )
    (net (code "79") (name "unconnected-(U$2A-GPIO_45-PadP8.11)") (class "Default")
      (node (ref "U$2") (pin "P8.11") (pinfunction "GPIO_45_P8.11") (pintype "bidirectional"))
    )
    (net (code "80") (name "unconnected-(U$2A-GPIO_46-PadP8.16)") (class "Default")
      (node (ref "U$2") (pin "P8.16") (pinfunction "GPIO_46_P8.16") (pintype "bidirectional"))
    )
    (net (code "81") (name "unconnected-(U$2A-GPIO_47-PadP8.15)") (class "Default")
      (node (ref "U$2") (pin "P8.15") (pinfunction "GPIO_47_P8.15") (pintype "bidirectional"))
    )
    (net (code "82") (name "unconnected-(U$2A-GPIO_61-PadP8.26)") (class "Default")
      (node (ref "U$2") (pin "P8.26") (pinfunction "GPIO_61_P8.26") (pintype "bidirectional"))
    )
    (net (code "83") (name "unconnected-(U$2A-GPIO_62-PadP8.21)") (class "Default")
      (node (ref "U$2") (pin "P8.21") (pinfunction "GPIO_62_P8.21") (pintype "bidirectional"))
    )
    (net (code "84") (name "unconnected-(U$2A-GPIO_63-PadP8.20)") (class "Default")
      (node (ref "U$2") (pin "P8.20") (pinfunction "GPIO_63_P8.20") (pintype "bidirectional"))
    )
    (net (code "85") (name "unconnected-(U$2A-GPIO_65-PadP8.18)") (class "Default")
      (node (ref "U$2") (pin "P8.18") (pinfunction "GPIO_65_P8.18") (pintype "bidirectional"))
    )
    (net (code "86") (name "unconnected-(U$2A-GPIO_66-PadP8.7)") (class "Default")
      (node (ref "U$2") (pin "P8.7") (pinfunction "GPIO_66_P8.7") (pintype "bidirectional"))
    )
    (net (code "87") (name "unconnected-(U$2A-GPIO_67-PadP8.8)") (class "Default")
      (node (ref "U$2") (pin "P8.8") (pinfunction "GPIO_67_P8.8") (pintype "bidirectional"))
    )
    (net (code "88") (name "unconnected-(U$2A-GPIO_68-PadP8.10)") (class "Default")
      (node (ref "U$2") (pin "P8.10") (pinfunction "GPIO_68_P8.10") (pintype "bidirectional"))
    )
    (net (code "89") (name "unconnected-(U$2A-GPIO_69-PadP8.9)") (class "Default")
      (node (ref "U$2") (pin "P8.9") (pinfunction "GPIO_69_P8.9") (pintype "bidirectional"))
    )
    (net (code "90") (name "unconnected-(U$2A-GPIO_70-PadP8.45)") (class "Default")
      (node (ref "U$2") (pin "P8.45") (pinfunction "GPIO_70_P8.45") (pintype "bidirectional"))
    )
    (net (code "91") (name "unconnected-(U$2A-GPIO_71-PadP8.46)") (class "Default")
      (node (ref "U$2") (pin "P8.46") (pinfunction "GPIO_71_P8.46") (pintype "bidirectional"))
    )
    (net (code "92") (name "unconnected-(U$2A-GPIO_72-PadP8.43)") (class "Default")
      (node (ref "U$2") (pin "P8.43") (pinfunction "GPIO_72_P8.43") (pintype "bidirectional"))
    )
    (net (code "93") (name "unconnected-(U$2A-GPIO_73-PadP8.44)") (class "Default")
      (node (ref "U$2") (pin "P8.44") (pinfunction "GPIO_73_P8.44") (pintype "bidirectional"))
    )
    (net (code "94") (name "unconnected-(U$2A-GPIO_74-PadP8.41)") (class "Default")
      (node (ref "U$2") (pin "P8.41") (pinfunction "GPIO_74_P8.41") (pintype "bidirectional"))
    )
    (net (code "95") (name "unconnected-(U$2A-GPIO_75-PadP8.42)") (class "Default")
      (node (ref "U$2") (pin "P8.42") (pinfunction "GPIO_75_P8.42") (pintype "bidirectional"))
    )
    (net (code "96") (name "unconnected-(U$2A-GPIO_76-PadP8.39)") (class "Default")
      (node (ref "U$2") (pin "P8.39") (pinfunction "GPIO_76_P8.39") (pintype "bidirectional"))
    )
    (net (code "97") (name "unconnected-(U$2A-GPIO_77-PadP8.40)") (class "Default")
      (node (ref "U$2") (pin "P8.40") (pinfunction "GPIO_77_P8.40") (pintype "bidirectional"))
    )
    (net (code "98") (name "unconnected-(U$2A-GPIO_80-PadP8.36)") (class "Default")
      (node (ref "U$2") (pin "P8.36") (pinfunction "GPIO_80_P8.36") (pintype "bidirectional"))
    )
    (net (code "99") (name "unconnected-(U$2A-GPIO_81-PadP8.34)") (class "Default")
      (node (ref "U$2") (pin "P8.34") (pinfunction "GPIO_81_P8.34") (pintype "bidirectional"))
    )
    (net (code "100") (name "unconnected-(U$2A-GPIO_86-PadP8.27)") (class "Default")
      (node (ref "U$2") (pin "P8.27") (pinfunction "GPIO_86_P8.27") (pintype "bidirectional"))
    )
    (net (code "101") (name "unconnected-(U$2A-GPIO_87-PadP8.29)") (class "Default")
      (node (ref "U$2") (pin "P8.29") (pinfunction "GPIO_87_P8.29") (pintype "bidirectional"))
    )
    (net (code "102") (name "unconnected-(U$2A-GPIO_88-PadP8.28)") (class "Default")
      (node (ref "U$2") (pin "P8.28") (pinfunction "GPIO_88_P8.28") (pintype "bidirectional"))
    )
    (net (code "103") (name "unconnected-(U$2A-GPIO_89-PadP8.30)") (class "Default")
      (node (ref "U$2") (pin "P8.30") (pinfunction "GPIO_89_P8.30") (pintype "bidirectional"))
    )
    (net (code "104") (name "unconnected-(U$2B-AIN0-PadP9.39)") (class "Default")
      (node (ref "U$2") (pin "P9.39") (pinfunction "AIN0_P9.39") (pintype "bidirectional"))
    )
    (net (code "105") (name "unconnected-(U$2B-AIN1-PadP9.40)") (class "Default")
      (node (ref "U$2") (pin "P9.40") (pinfunction "AIN1_P9.40") (pintype "bidirectional"))
    )
    (net (code "106") (name "unconnected-(U$2B-AIN2-PadP9.37)") (class "Default")
      (node (ref "U$2") (pin "P9.37") (pinfunction "AIN2_P9.37") (pintype "bidirectional"))
    )
    (net (code "107") (name "unconnected-(U$2B-AIN3-PadP9.38)") (class "Default")
      (node (ref "U$2") (pin "P9.38") (pinfunction "AIN3_P9.38") (pintype "bidirectional"))
    )
    (net (code "108") (name "unconnected-(U$2B-AIN4-PadP9.33)") (class "Default")
      (node (ref "U$2") (pin "P9.33") (pinfunction "AIN4_P9.33") (pintype "bidirectional"))
    )
    (net (code "109") (name "unconnected-(U$2B-AIN5-PadP9.36)") (class "Default")
      (node (ref "U$2") (pin "P9.36") (pinfunction "AIN5_P9.36") (pintype "bidirectional"))
    )
    (net (code "110") (name "unconnected-(U$2B-AIN6-PadP9.35)") (class "Default")
      (node (ref "U$2") (pin "P9.35") (pinfunction "AIN6_P9.35") (pintype "bidirectional"))
    )
    (net (code "111") (name "unconnected-(U$2B-GNDA_ADC-PadP9.34)") (class "Default")
      (node (ref "U$2") (pin "P9.34") (pinfunction "GNDA_ADC_P9.34") (pintype "bidirectional"))
    )
    (net (code "112") (name "unconnected-(U$2B-GPIO_2-PadP9.22)") (class "Default")
      (node (ref "U$2") (pin "P9.22") (pinfunction "GPIO_2_P9.22") (pintype "bidirectional"))
    )
    (net (code "113") (name "unconnected-(U$2B-GPIO_3-PadP9.21)") (class "Default")
      (node (ref "U$2") (pin "P9.21") (pinfunction "GPIO_3_P9.21") (pintype "bidirectional"))
    )
    (net (code "114") (name "unconnected-(U$2B-GPIO_14-PadP9.26)") (class "Default")
      (node (ref "U$2") (pin "P9.26") (pinfunction "GPIO_14_P9.26") (pintype "bidirectional"))
    )
    (net (code "115") (name "unconnected-(U$2B-GPIO_15-PadP9.24)") (class "Default")
      (node (ref "U$2") (pin "P9.24") (pinfunction "GPIO_15_P9.24") (pintype "bidirectional"))
    )
    (net (code "116") (name "unconnected-(U$2B-GPIO_20-PadP9.41)") (class "Default")
      (node (ref "U$2") (pin "P9.41") (pinfunction "GPIO_20_P9.41") (pintype "bidirectional"))
    )
    (net (code "117") (name "unconnected-(U$2B-GPIO_30-PadP9.11)") (class "Default")
      (node (ref "U$2") (pin "P9.11") (pinfunction "GPIO_30_P9.11") (pintype "bidirectional"))
    )
    (net (code "118") (name "unconnected-(U$2B-GPIO_31-PadP9.13)") (class "Default")
      (node (ref "U$2") (pin "P9.13") (pinfunction "GPIO_31_P9.13") (pintype "bidirectional"))
    )
    (net (code "119") (name "unconnected-(U$2B-GPIO_40-PadP9.14)") (class "Default")
      (node (ref "U$2") (pin "P9.14") (pinfunction "GPIO_40_P9.14") (pintype "bidirectional"))
    )
    (net (code "120") (name "unconnected-(U$2B-GPIO_48-PadP9.15)") (class "Default")
      (node (ref "U$2") (pin "P9.15") (pinfunction "GPIO_48_P9.15") (pintype "bidirectional"))
    )
    (net (code "121") (name "unconnected-(U$2B-GPIO_49-PadP9.23)") (class "Default")
      (node (ref "U$2") (pin "P9.23") (pinfunction "GPIO_49_P9.23") (pintype "bidirectional"))
    )
    (net (code "122") (name "unconnected-(U$2B-GPIO_51-PadP9.16)") (class "Default")
      (node (ref "U$2") (pin "P9.16") (pinfunction "GPIO_51_P9.16") (pintype "bidirectional"))
    )
    (net (code "123") (name "unconnected-(U$2B-GPIO_60-PadP9.12)") (class "Default")
      (node (ref "U$2") (pin "P9.12") (pinfunction "GPIO_60_P9.12") (pintype "bidirectional"))
    )
    (net (code "124") (name "unconnected-(U$2B-GPIO_117-PadP9.25)") (class "Default")
      (node (ref "U$2") (pin "P9.25") (pinfunction "GPIO_117_P9.25") (pintype "bidirectional"))
    )
    (net (code "125") (name "unconnected-(U$2B-GPIO_125-PadP9.27)") (class "Default")
      (node (ref "U$2") (pin "P9.27") (pinfunction "GPIO_125_P9.27") (pintype "bidirectional"))
    )
    (net (code "126") (name "unconnected-(U$2B-PWR_BUT-PadP9.9)") (class "Default")
      (node (ref "U$2") (pin "P9.9") (pinfunction "PWR_BUT_P9.9") (pintype "bidirectional"))
    )
    (net (code "127") (name "unconnected-(U$2B-SYS_5V-PadP9.7)") (class "Default")
      (node (ref "U$2") (pin "P9.7") (pinfunction "SYS_5V_P9.7") (pintype "bidirectional"))
    )
    (net (code "128") (name "unconnected-(U$2B-SYS_5V-PadP9.8)") (class "Default")
      (node (ref "U$2") (pin "P9.8") (pinfunction "SYS_5V_P9.8") (pintype "bidirectional"))
    )
    (net (code "129") (name "unconnected-(U$2B-VDD_5V-PadP9.5)") (class "Default")
      (node (ref "U$2") (pin "P9.5") (pinfunction "VDD_5V_P9.5") (pintype "bidirectional"))
    )
    (net (code "130") (name "unconnected-(U$2B-VDD_5V-PadP9.6)") (class "Default")
      (node (ref "U$2") (pin "P9.6") (pinfunction "VDD_5V_P9.6") (pintype "bidirectional"))
    )
    (net (code "131") (name "unconnected-(U$2B-VDD_ADC-PadP9.32)") (class "Default")
      (node (ref "U$2") (pin "P9.32") (pinfunction "VDD_ADC_P9.32") (pintype "bidirectional"))
    )
    (net (code "132") (name "unconnected-(U$3-~{INT}-Pad17)") (class "Default")
      (node (ref "U$3") (pin "17") (pinfunction "~{INT}_17") (pintype "output"))
    )
    (net (code "133") (name "unconnected-(U$5-HOLD_~{THRU}-Pad5)") (class "Default")
      (node (ref "U$5") (pin "5") (pinfunction "HOLD_~{THRU}_5") (pintype "bidirectional"))
    )
    (net (code "134") (name "unconnected-(U$5-SHDN-Pad1)") (class "Default")
      (node (ref "U$5") (pin "1") (pinfunction "SHDN_1") (pintype "bidirectional"))
    )
    (net (code "135") (name "unconnected-(U$6-HOLD_~{THRU}-Pad5)") (class "Default")
      (node (ref "U$6") (pin "5") (pinfunction "HOLD_~{THRU}_5") (pintype "bidirectional"))
    )
    (net (code "136") (name "unconnected-(U$6-SHDN-Pad1)") (class "Default")
      (node (ref "U$6") (pin "1") (pinfunction "SHDN_1") (pintype "bidirectional"))
    )
    (net (code "137") (name "unconnected-(U$7-HOLD_~{THRU}-Pad5)") (class "Default")
      (node (ref "U$7") (pin "5") (pinfunction "HOLD_~{THRU}_5") (pintype "bidirectional"))
    )
    (net (code "138") (name "unconnected-(U$7-SHDN-Pad1)") (class "Default")
      (node (ref "U$7") (pin "1") (pinfunction "SHDN_1") (pintype "bidirectional"))
    )
    (net (code "139") (name "unconnected-(U$8-HOLD_~{THRU}-Pad5)") (class "Default")
      (node (ref "U$8") (pin "5") (pinfunction "HOLD_~{THRU}_5") (pintype "bidirectional"))
    )
    (net (code "140") (name "unconnected-(U$8-SHDN-Pad1)") (class "Default")
      (node (ref "U$8") (pin "1") (pinfunction "SHDN_1") (pintype "bidirectional"))
    )
    (net (code "141") (name "unconnected-(U3-DEN_A{slash}G-Pad13)") (class "Default")
      (node (ref "U3") (pin "13") (pinfunction "DEN_A/G_13") (pintype "bidirectional"))
    )
    (net (code "142") (name "unconnected-(U3-DRDY_M-Pad9)") (class "Default")
      (node (ref "U3") (pin "9") (pinfunction "DRDY_M_9") (pintype "bidirectional"))
    )
    (net (code "143") (name "unconnected-(U3-INT1_A{slash}G-Pad11)") (class "Default")
      (node (ref "U3") (pin "11") (pinfunction "INT1_A/G_11") (pintype "bidirectional"))
    )
    (net (code "144") (name "unconnected-(U3-INT2_A{slash}G-Pad12)") (class "Default")
      (node (ref "U3") (pin "12") (pinfunction "INT2_A/G_12") (pintype "bidirectional"))
    )
    (net (code "145") (name "unconnected-(U3-INT_M-Pad10)") (class "Default")
      (node (ref "U3") (pin "10") (pinfunction "INT_M_10") (pintype "bidirectional"))
    )
    (net (code "146") (name "unconnected-(X2-S1-PadS@1)") (class "Default")
      (node (ref "X2") (pin "S@1") (pinfunction "S1_S@1") (pintype "passive"))
    )
    (net (code "147") (name "unconnected-(X2-S2-PadS@2)") (class "Default")
      (node (ref "X2") (pin "S@2") (pinfunction "S2_S@2") (pintype "passive"))
    )
  )
)
